# TPS26600_Module.net
KiCad netlist of a schematic drawn in EAGLE
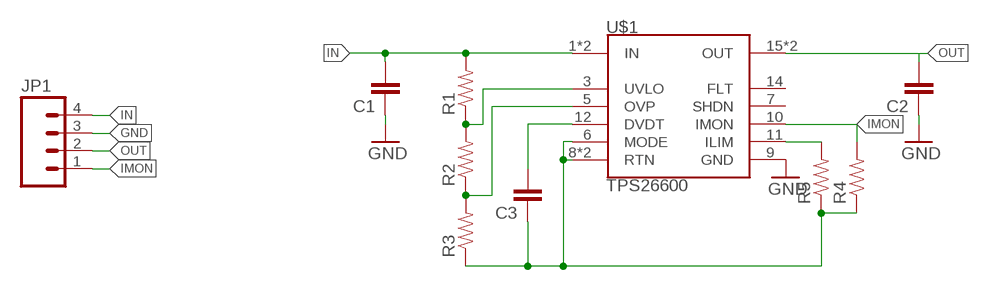
[diagram p0: schematic, sheet 1]

(export (version "E")
  (design (tool "Eeschema 10.0.6"))
  (components
    (comp (ref "C1")
      (value "CAP0603-CAP")
      (footprint "eagle-import:0603-CAP")
      (libsource (lib "eagle-import") (part "CAP0603-CAP"))
    )
    (comp (ref "C2")
      (value "CAP0603-CAP")
      (footprint "eagle-import:0603-CAP")
      (libsource (lib "eagle-import") (part "CAP0603-CAP"))
    )
    (comp (ref "C3")
      (value "CAP0603-CAP")
      (footprint "eagle-import:0603-CAP")
      (libsource (lib "eagle-import") (part "CAP0603-CAP"))
    )
    (comp (ref "JP1")
      (value "M04_SLIM")
      (footprint "eagle-import:1X04_SLIM")
      (libsource (lib "eagle-import") (part "M04_SLIM"))
    )
    (comp (ref "R1")
      (value "RESISTOR0603")
      (footprint "eagle-import:0603-RES")
      (libsource (lib "eagle-import") (part "RESISTOR0603"))
    )
    (comp (ref "R2")
      (value "RESISTOR0603")
      (footprint "eagle-import:0603-RES")
      (libsource (lib "eagle-import") (part "RESISTOR0603"))
    )
    (comp (ref "R3")
      (value "RESISTOR0603")
      (footprint "eagle-import:0603-RES")
      (libsource (lib "eagle-import") (part "RESISTOR0603"))
    )
    (comp (ref "R4")
      (value "RESISTOR0603")
      (footprint "eagle-import:0603-RES")
      (libsource (lib "eagle-import") (part "RESISTOR0603"))
    )
    (comp (ref "R5")
      (value "RESISTOR0603")
      (footprint "eagle-import:0603-RES")
      (libsource (lib "eagle-import") (part "RESISTOR0603"))
    )
    (comp (ref "U$1")
      (value "TPS26600")
      (footprint "eagle-import:HTSSOP-16")
      (libsource (lib "eagle-import") (part "TPS26600"))
    )
  )
  (nets
    (net (code "1") (name "GND") (class "Default")
      (node (ref "C1") (pin "1") (pinfunction "1_1") (pintype "passive"))
      (node (ref "C2") (pin "1") (pinfunction "1_1") (pintype "passive"))
      (node (ref "JP1") (pin "3") (pinfunction "3_3") (pintype "passive"))
      (node (ref "U$1") (pin "9") (pinfunction "GND_9") (pintype "bidirectional"))
    )
    (net (code "2") (name "IMON") (class "Default")
      (node (ref "JP1") (pin "1") (pinfunction "1_1") (pintype "passive"))
      (node (ref "R4") (pin "2") (pinfunction "2_2") (pintype "passive"))
      (node (ref "U$1") (pin "10") (pinfunction "IMON_10") (pintype "bidirectional"))
    )
    (net (code "3") (name "IN") (class "Default")
      (node (ref "C1") (pin "2") (pinfunction "2_2") (pintype "passive"))
      (node (ref "JP1") (pin "4") (pinfunction "4_4") (pintype "passive"))
      (node (ref "R1") (pin "2") (pinfunction "2_2") (pintype "passive"))
      (node (ref "U$1") (pin "1") (pinfunction "IN_1") (pintype "bidirectional"))
      (node (ref "U$1") (pin "2") (pinfunction "IN_2") (pintype "bidirectional"))
    )
    (net (code "4") (name "Net-(U$1-DVDT)") (class "Default")
      (node (ref "C3") (pin "2") (pinfunction "2_2") (pintype "passive"))
      (node (ref "U$1") (pin "12") (pinfunction "DVDT_12") (pintype "bidirectional"))
    )
    (net (code "5") (name "Net-(U$1-ILIM)") (class "Default")
      (node (ref "R5") (pin "2") (pinfunction "2_2") (pintype "passive"))
      (node (ref "U$1") (pin "11") (pinfunction "ILIM_11") (pintype "bidirectional"))
    )
    (net (code "6") (name "Net-(U$1-MODE)") (class "Default")
      (node (ref "C3") (pin "1") (pinfunction "1_1") (pintype "passive"))
      (node (ref "R3") (pin "1") (pinfunction "1_1") (pintype "passive"))
      (node (ref "R4") (pin "1") (pinfunction "1_1") (pintype "passive"))
      (node (ref "R5") (pin "1") (pinfunction "1_1") (pintype "passive"))
      (node (ref "U$1") (pin "6") (pinfunction "MODE_6") (pintype "bidirectional"))
      (node (ref "U$1") (pin "8") (pinfunction "RTN_8") (pintype "bidirectional"))
      (node (ref "U$1") (pin "PAD") (pinfunction "RTN_PAD") (pintype "bidirectional"))
    )
    (net (code "7") (name "Net-(U$1-OVP)") (class "Default")
      (node (ref "R2") (pin "1") (pinfunction "1_1") (pintype "passive"))
      (node (ref "R3") (pin "2") (pinfunction "2_2") (pintype "passive"))
      (node (ref "U$1") (pin "5") (pinfunction "OVP_5") (pintype "bidirectional"))
    )
    (net (code "8") (name "Net-(U$1-UVLO)") (class "Default")
      (node (ref "R1") (pin "1") (pinfunction "1_1") (pintype "passive"))
      (node (ref "R2") (pin "2") (pinfunction "2_2") (pintype "passive"))
      (node (ref "U$1") (pin "3") (pinfunction "UVLO_3") (pintype "bidirectional"))
    )
    (net (code "9") (name "OUT") (class "Default")
      (node (ref "C2") (pin "2") (pinfunction "2_2") (pintype "passive"))
      (node (ref "JP1") (pin "2") (pinfunction "2_2") (pintype "passive"))
      (node (ref "U$1") (pin "15") (pinfunction "OUT_15") (pintype "bidirectional"))
      (node (ref "U$1") (pin "16") (pinfunction "OUT_16") (pintype "bidirectional"))
    )
    (net (code "10") (name "unconnected-(U$1-FLT-Pad14)") (class "Default")
      (node (ref "U$1") (pin "14") (pinfunction "FLT_14") (pintype "bidirectional"))
    )
    (net (code "11") (name "unconnected-(U$1-SHDN-Pad7)") (class "Default")
      (node (ref "U$1") (pin "7") (pinfunction "SHDN_7") (pintype "bidirectional"))
    )
  )
)
